# CCM_0020_receiver.net
KiCad netlist of a schematic drawn in EAGLE
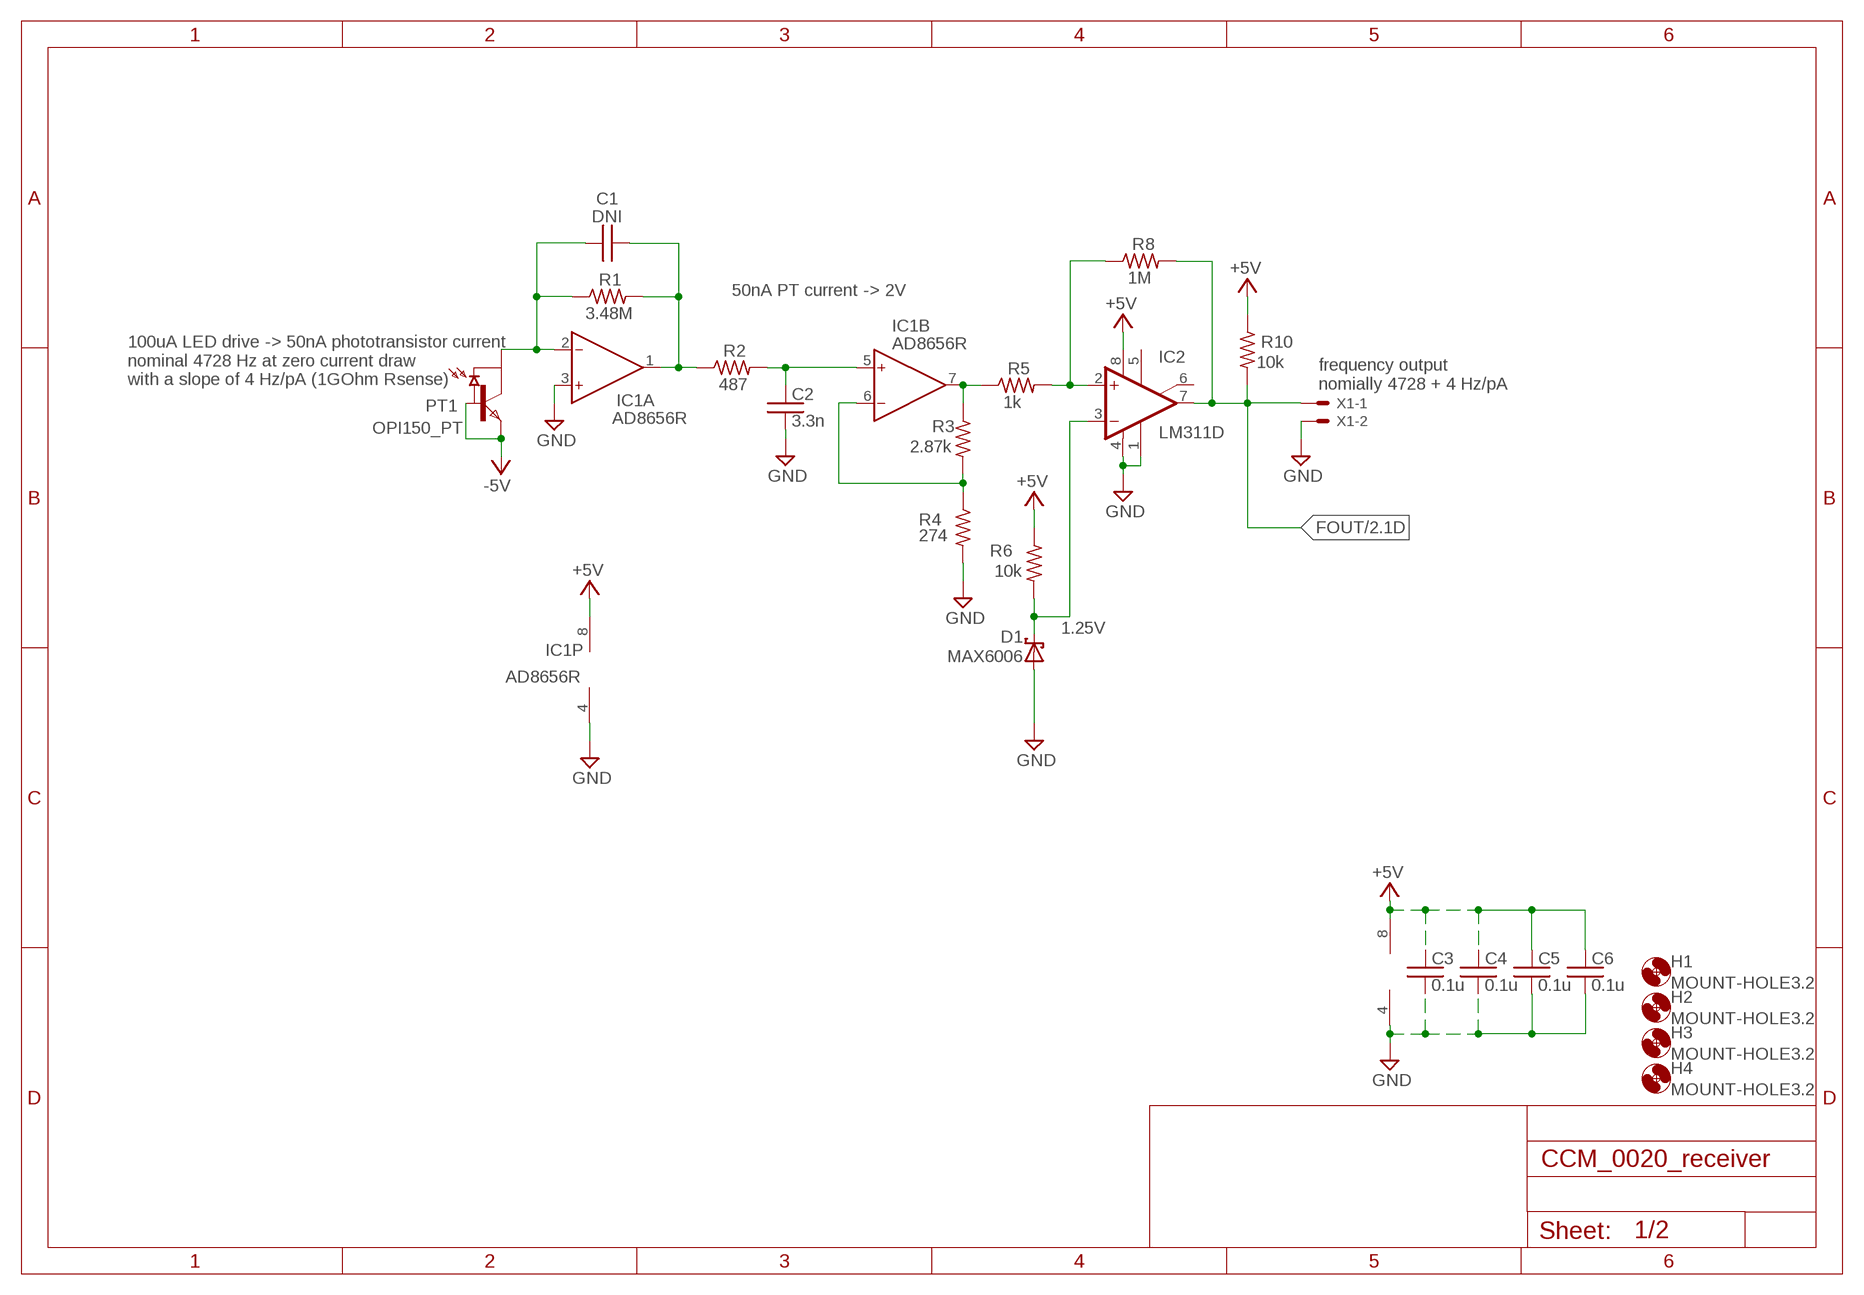
[diagram p0: schematic, sheet 1]
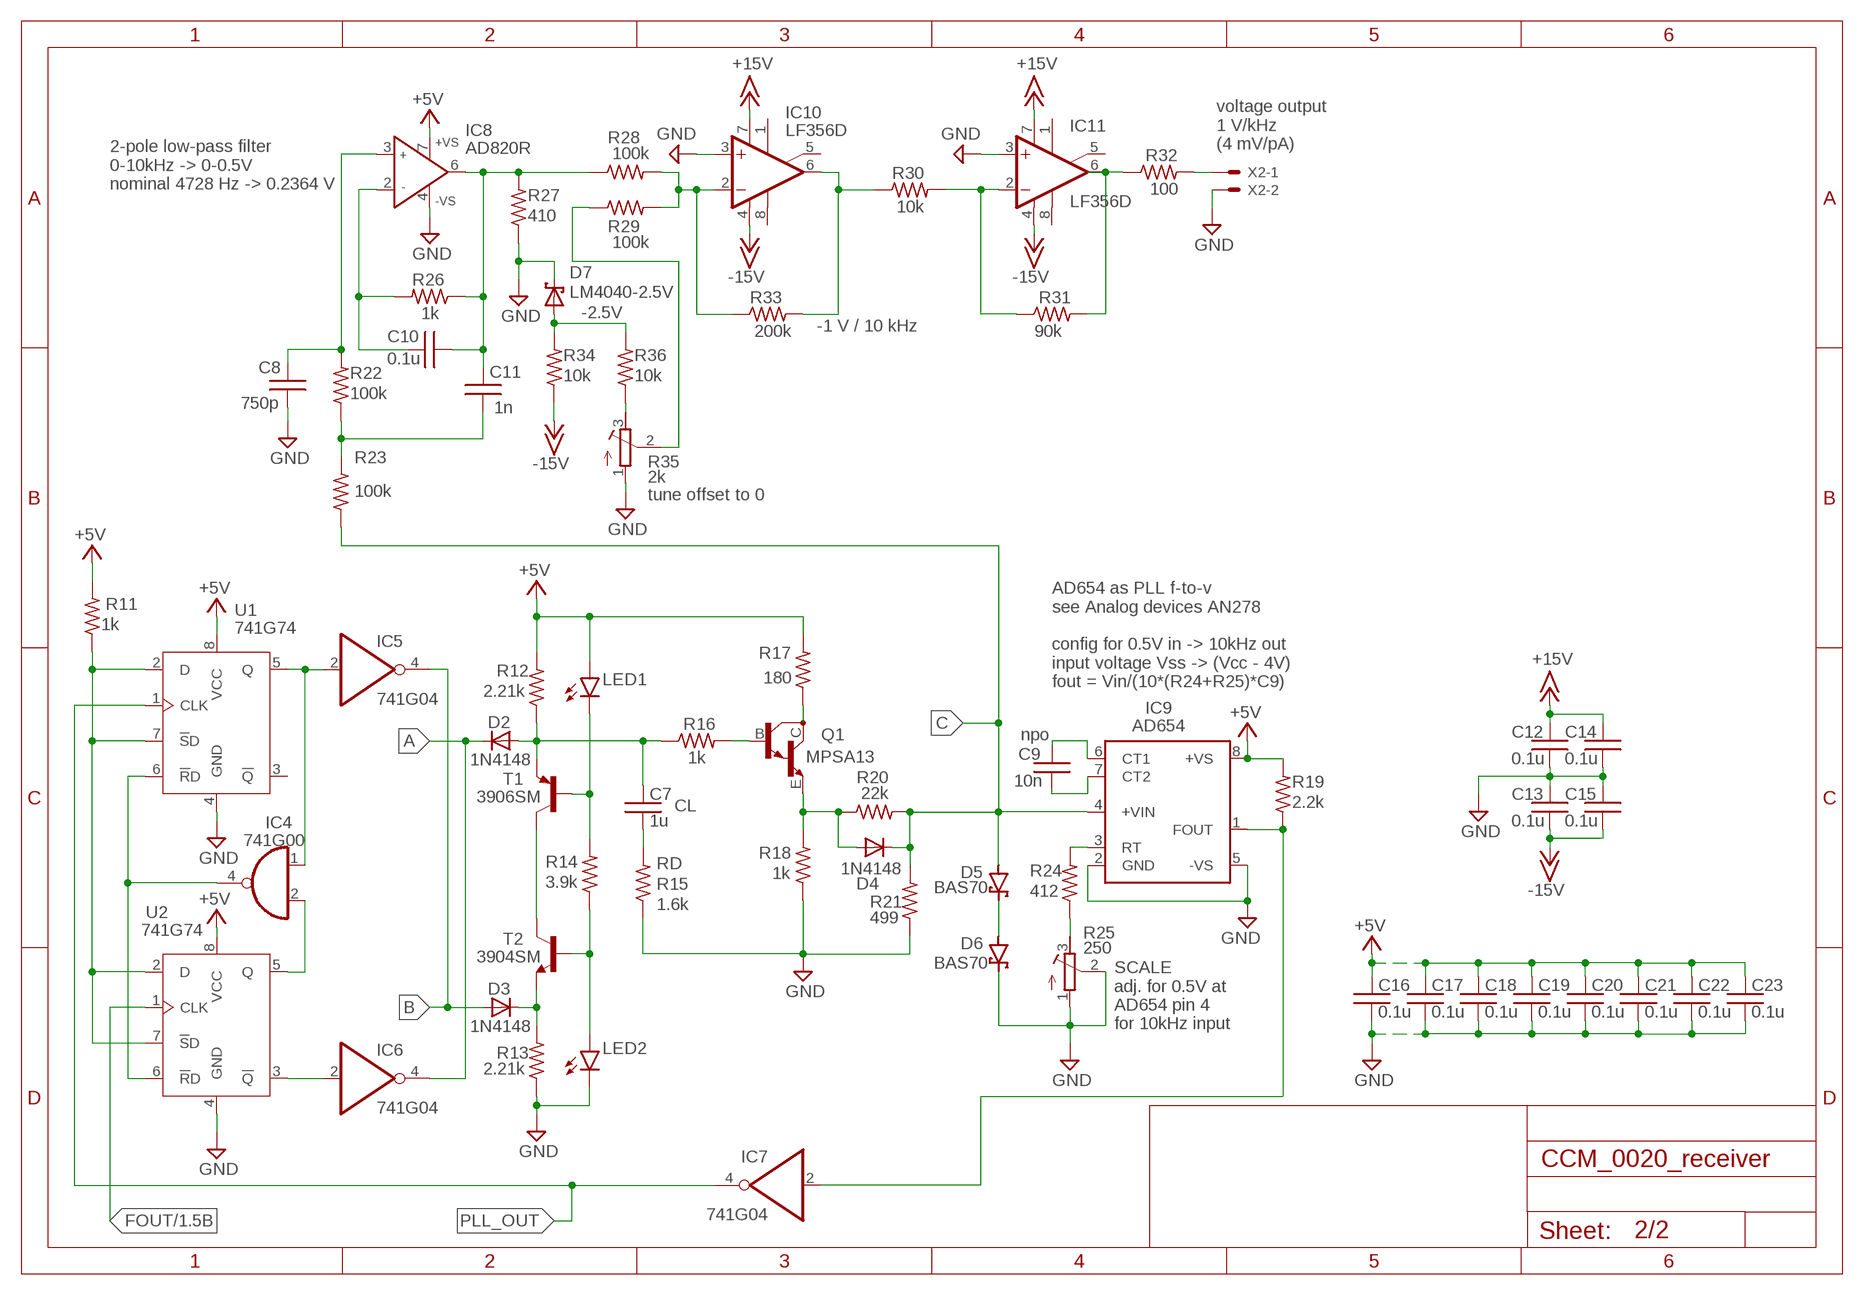
[diagram p1: schematic, sheet 2]

(export (version "E")
  (design (tool "Eeschema 10.0.6"))
  (components
    (comp (ref "C1")
      (value "DNI")
      (footprint "eagle-import:0603")
      (libsource (lib "eagle-import") (part "C0603"))
    )
    (comp (ref "C2")
      (value "3.3n")
      (footprint "eagle-import:0603")
      (libsource (lib "eagle-import") (part "C0603"))
    )
    (comp (ref "C3")
      (value "0.1u")
      (footprint "eagle-import:0603")
      (libsource (lib "eagle-import") (part "C0603"))
    )
    (comp (ref "C4")
      (value "0.1u")
      (footprint "eagle-import:0603")
      (libsource (lib "eagle-import") (part "C0603"))
    )
    (comp (ref "C5")
      (value "0.1u")
      (footprint "eagle-import:0603")
      (libsource (lib "eagle-import") (part "C0603"))
    )
    (comp (ref "C6")
      (value "0.1u")
      (footprint "eagle-import:0603")
      (libsource (lib "eagle-import") (part "C0603"))
    )
    (comp (ref "D1")
      (value "MAX6006")
      (footprint "eagle-import:SOT23")
      (libsource (lib "eagle-import") (part "LM4040"))
    )
    (comp (ref "H1")
      (value "MOUNT-HOLE3.2")
      (footprint "eagle-import:3,2")
      (libsource (lib "eagle-import") (part "MOUNT-HOLE3.2"))
    )
    (comp (ref "H2")
      (value "MOUNT-HOLE3.2")
      (footprint "eagle-import:3,2")
      (libsource (lib "eagle-import") (part "MOUNT-HOLE3.2"))
    )
    (comp (ref "H3")
      (value "MOUNT-HOLE3.2")
      (footprint "eagle-import:3,2")
      (libsource (lib "eagle-import") (part "MOUNT-HOLE3.2"))
    )
    (comp (ref "H4")
      (value "MOUNT-HOLE3.2")
      (footprint "eagle-import:3,2")
      (libsource (lib "eagle-import") (part "MOUNT-HOLE3.2"))
    )
    (comp (ref "IC1")
      (value "AD8656R")
      (footprint "eagle-import:SO8")
      (fields (field (name "MPN") "AD8656ARZ"))
      (libsource (lib "eagle-import") (part "AD8656R"))
    )
    (comp (ref "IC2")
      (value "LM311D")
      (footprint "eagle-import:SO08")
      (libsource (lib "eagle-import") (part "LM311D"))
    )
    (comp (ref "IC3")
      (value "LT1495")
      (footprint "eagle-import:SO08")
      (libsource (lib "eagle-import") (part "LM393D"))
    )
    (comp (ref "PT1")
      (value "OPI150_PT")
      (footprint "eagle-import:OPI150_PHOTOTRANSISTOR")
      (libsource (lib "eagle-import") (part "OPI150_PHOTOTRANSISTOR"))
    )
    (comp (ref "R1")
      (value "3.48M")
      (footprint "eagle-import:0603")
      (libsource (lib "eagle-import") (part "R0603"))
    )
    (comp (ref "R2")
      (value "487")
      (footprint "eagle-import:0603")
      (libsource (lib "eagle-import") (part "R0603"))
    )
    (comp (ref "R3")
      (value "2.87k")
      (footprint "eagle-import:0603")
      (libsource (lib "eagle-import") (part "R0603"))
    )
    (comp (ref "R4")
      (value "274")
      (footprint "eagle-import:0603")
      (libsource (lib "eagle-import") (part "R0603"))
    )
    (comp (ref "R5")
      (value "1k")
      (footprint "eagle-import:0603")
      (libsource (lib "eagle-import") (part "R0603"))
    )
    (comp (ref "R6")
      (value "10k")
      (footprint "eagle-import:0603")
      (libsource (lib "eagle-import") (part "R0603"))
    )
    (comp (ref "R8")
      (value "1M")
      (footprint "eagle-import:0603")
      (libsource (lib "eagle-import") (part "R0603"))
    )
    (comp (ref "R10")
      (value "10k")
      (footprint "eagle-import:0603")
      (libsource (lib "eagle-import") (part "R0603"))
    )
    (comp (ref "X1")
      (value "22-23-2021")
      (footprint "eagle-import:22-23-2021")
      (fields (field (name "MF") "MOLEX"))
      (libsource (lib "eagle-import") (part "22-23-2021"))
    )
    (comp (ref "C7")
      (value "1u")
      (footprint "eagle-import:0603")
      (libsource (lib "eagle-import") (part "C0603"))
    )
    (comp (ref "C8")
      (value "750p")
      (footprint "eagle-import:0603")
      (libsource (lib "eagle-import") (part "C0603"))
    )
    (comp (ref "C9")
      (value "10n")
      (footprint "eagle-import:0603")
      (libsource (lib "eagle-import") (part "C0603"))
    )
    (comp (ref "C10")
      (value "0.1u")
      (footprint "eagle-import:0603")
      (libsource (lib "eagle-import") (part "C0603"))
    )
    (comp (ref "C11")
      (value "1n")
      (footprint "eagle-import:0603")
      (libsource (lib "eagle-import") (part "C0603"))
    )
    (comp (ref "C12")
      (value "0.1u")
      (footprint "eagle-import:0603")
      (libsource (lib "eagle-import") (part "C0603"))
    )
    (comp (ref "C13")
      (value "0.1u")
      (footprint "eagle-import:0603")
      (libsource (lib "eagle-import") (part "C0603"))
    )
    (comp (ref "C14")
      (value "0.1u")
      (footprint "eagle-import:0603")
      (libsource (lib "eagle-import") (part "C0603"))
    )
    (comp (ref "C15")
      (value "0.1u")
      (footprint "eagle-import:0603")
      (libsource (lib "eagle-import") (part "C0603"))
    )
    (comp (ref "C16")
      (value "0.1u")
      (footprint "eagle-import:0603")
      (libsource (lib "eagle-import") (part "C0603"))
    )
    (comp (ref "C17")
      (value "0.1u")
      (footprint "eagle-import:0603")
      (libsource (lib "eagle-import") (part "C0603"))
    )
    (comp (ref "C18")
      (value "0.1u")
      (footprint "eagle-import:0603")
      (libsource (lib "eagle-import") (part "C0603"))
    )
    (comp (ref "C19")
      (value "0.1u")
      (footprint "eagle-import:0603")
      (libsource (lib "eagle-import") (part "C0603"))
    )
    (comp (ref "C20")
      (value "0.1u")
      (footprint "eagle-import:0603")
      (libsource (lib "eagle-import") (part "C0603"))
    )
    (comp (ref "C21")
      (value "0.1u")
      (footprint "eagle-import:0603")
      (libsource (lib "eagle-import") (part "C0603"))
    )
    (comp (ref "C22")
      (value "0.1u")
      (footprint "eagle-import:0603")
      (libsource (lib "eagle-import") (part "C0603"))
    )
    (comp (ref "C23")
      (value "0.1u")
      (footprint "eagle-import:0603")
      (libsource (lib "eagle-import") (part "C0603"))
    )
    (comp (ref "D2")
      (value "1N4148")
      (footprint "eagle-import:SOD323_ST")
      (libsource (lib "eagle-import") (part "1N4148"))
    )
    (comp (ref "D3")
      (value "1N4148")
      (footprint "eagle-import:SOD323_ST")
      (libsource (lib "eagle-import") (part "1N4148"))
    )
    (comp (ref "D4")
      (value "1N4148")
      (footprint "eagle-import:SOD323_ST")
      (libsource (lib "eagle-import") (part "1N4148"))
    )
    (comp (ref "D5")
      (value "BAS70")
      (footprint "eagle-import:SOT23")
      (libsource (lib "eagle-import") (part "BAS70"))
    )
    (comp (ref "D6")
      (value "BAS70")
      (footprint "eagle-import:SOT23")
      (libsource (lib "eagle-import") (part "BAS70"))
    )
    (comp (ref "D7")
      (value "LM4040-2.5V")
      (footprint "eagle-import:SOT23")
      (libsource (lib "eagle-import") (part "LM4040"))
    )
    (comp (ref "IC4")
      (value "741G00")
      (footprint "eagle-import:SOT23-5")
      (libsource (lib "eagle-import") (part "741G00DBVAHC"))
    )
    (comp (ref "IC5")
      (value "741G04")
      (footprint "eagle-import:SOT23-5")
      (libsource (lib "eagle-import") (part "741G04DBVAHC"))
    )
    (comp (ref "IC6")
      (value "741G04")
      (footprint "eagle-import:SOT23-5")
      (libsource (lib "eagle-import") (part "741G04DBVAHC"))
    )
    (comp (ref "IC7")
      (value "741G04")
      (footprint "eagle-import:SOT23-5")
      (libsource (lib "eagle-import") (part "741G04DBVAHC"))
    )
    (comp (ref "IC8")
      (value "AD820R")
      (footprint "eagle-import:SO8")
      (libsource (lib "eagle-import") (part "AD820R"))
    )
    (comp (ref "IC9")
      (value "AD654")
      (footprint "eagle-import:SO08")
      (libsource (lib "eagle-import") (part "AD654"))
    )
    (comp (ref "IC10")
      (value "LF356D")
      (footprint "eagle-import:SO08")
      (libsource (lib "eagle-import") (part "LF356D"))
    )
    (comp (ref "IC11")
      (value "LF356D")
      (footprint "eagle-import:SO08")
      (libsource (lib "eagle-import") (part "LF356D"))
    )
    (comp (ref "LED1")
      (value "LEDCHIP-LED0603")
      (footprint "eagle-import:CHIP-LED0603")
      (libsource (lib "eagle-import") (part "LEDCHIP-LED0603"))
    )
    (comp (ref "LED2")
      (value "LEDCHIP-LED0603")
      (footprint "eagle-import:CHIP-LED0603")
      (libsource (lib "eagle-import") (part "LEDCHIP-LED0603"))
    )
    (comp (ref "Q1")
      (value "MPSA13")
      (footprint "eagle-import:SOT23-BEC")
      (libsource (lib "eagle-import") (part "MMBTA13LT1"))
    )
    (comp (ref "R11")
      (value "1k")
      (footprint "eagle-import:0603")
      (libsource (lib "eagle-import") (part "R0603"))
    )
    (comp (ref "R12")
      (value "2.21k")
      (footprint "eagle-import:0603")
      (libsource (lib "eagle-import") (part "R0603"))
    )
    (comp (ref "R13")
      (value "2.21k")
      (footprint "eagle-import:0603")
      (libsource (lib "eagle-import") (part "R0603"))
    )
    (comp (ref "R14")
      (value "3.9k")
      (footprint "eagle-import:0603")
      (libsource (lib "eagle-import") (part "R0603"))
    )
    (comp (ref "R15")
      (value "1.6k")
      (footprint "eagle-import:0603")
      (libsource (lib "eagle-import") (part "R0603"))
    )
    (comp (ref "R16")
      (value "1k")
      (footprint "eagle-import:0603")
      (libsource (lib "eagle-import") (part "R0603"))
    )
    (comp (ref "R17")
      (value "180")
      (footprint "eagle-import:0603")
      (libsource (lib "eagle-import") (part "R0603"))
    )
    (comp (ref "R18")
      (value "1k")
      (footprint "eagle-import:0603")
      (libsource (lib "eagle-import") (part "R0603"))
    )
    (comp (ref "R19")
      (value "2.2k")
      (footprint "eagle-import:0603")
      (libsource (lib "eagle-import") (part "R0603"))
    )
    (comp (ref "R20")
      (value "22k")
      (footprint "eagle-import:0603")
      (libsource (lib "eagle-import") (part "R0603"))
    )
    (comp (ref "R21")
      (value "499")
      (footprint "eagle-import:0603")
      (libsource (lib "eagle-import") (part "R0603"))
    )
    (comp (ref "R22")
      (value "100k")
      (footprint "eagle-import:0603")
      (libsource (lib "eagle-import") (part "R0603"))
    )
    (comp (ref "R23")
      (value "100k")
      (footprint "eagle-import:0603")
      (libsource (lib "eagle-import") (part "R0603"))
    )
    (comp (ref "R24")
      (value "412")
      (footprint "eagle-import:0603")
      (libsource (lib "eagle-import") (part "R0603"))
    )
    (comp (ref "R25")
      (value "250")
      (footprint "eagle-import:RTRIM64Y")
      (libsource (lib "eagle-import") (part "R-TRIMM64Y"))
    )
    (comp (ref "R26")
      (value "1k")
      (footprint "eagle-import:0603")
      (libsource (lib "eagle-import") (part "R0603"))
    )
    (comp (ref "R27")
      (value "410")
      (footprint "eagle-import:0603")
      (libsource (lib "eagle-import") (part "R0603"))
    )
    (comp (ref "R28")
      (value "100k")
      (footprint "eagle-import:0603")
      (libsource (lib "eagle-import") (part "R0603"))
    )
    (comp (ref "R29")
      (value "100k")
      (footprint "eagle-import:0603")
      (libsource (lib "eagle-import") (part "R0603"))
    )
    (comp (ref "R30")
      (value "10k")
      (footprint "eagle-import:0603")
      (libsource (lib "eagle-import") (part "R0603"))
    )
    (comp (ref "R31")
      (value "90k")
      (footprint "eagle-import:0603")
      (libsource (lib "eagle-import") (part "R0603"))
    )
    (comp (ref "R32")
      (value "100")
      (footprint "eagle-import:0603")
      (libsource (lib "eagle-import") (part "R0603"))
    )
    (comp (ref "R33")
      (value "200k")
      (footprint "eagle-import:0603")
      (libsource (lib "eagle-import") (part "R0603"))
    )
    (comp (ref "R34")
      (value "10k")
      (footprint "eagle-import:0603")
      (libsource (lib "eagle-import") (part "R0603"))
    )
    (comp (ref "R35")
      (value "2k")
      (footprint "eagle-import:RTRIM64Y")
      (libsource (lib "eagle-import") (part "R-TRIMM64Y"))
    )
    (comp (ref "R36")
      (value "10k")
      (footprint "eagle-import:0603")
      (libsource (lib "eagle-import") (part "R0603"))
    )
    (comp (ref "T1")
      (value "3906SM")
      (footprint "eagle-import:SOT23-BEC")
      (libsource (lib "eagle-import") (part "-PNP-SOT23-BECMMBT3906LT1"))
    )
    (comp (ref "T2")
      (value "3904SM")
      (footprint "eagle-import:SOT23")
      (libsource (lib "eagle-import") (part "3904SM"))
    )
    (comp (ref "U1")
      (value "741G74")
      (footprint "eagle-import:TSSOP8")
      (libsource (lib "eagle-import") (part "741G74"))
    )
    (comp (ref "U2")
      (value "741G74")
      (footprint "eagle-import:TSSOP8")
      (libsource (lib "eagle-import") (part "741G74"))
    )
    (comp (ref "X2")
      (value "22-23-2021")
      (footprint "eagle-import:22-23-2021")
      (fields (field (name "MF") "MOLEX"))
      (libsource (lib "eagle-import") (part "22-23-2021"))
    )
  )
  (nets
    (net (code "1") (name "+5V") (class "Default")
      (node (ref "C16") (pin "1") (pinfunction "1_1") (pintype "passive"))
      (node (ref "C17") (pin "1") (pinfunction "1_1") (pintype "passive"))
      (node (ref "C18") (pin "1") (pinfunction "1_1") (pintype "passive"))
      (node (ref "C19") (pin "1") (pinfunction "1_1") (pintype "passive"))
      (node (ref "C20") (pin "1") (pinfunction "1_1") (pintype "passive"))
      (node (ref "C21") (pin "1") (pinfunction "1_1") (pintype "passive"))
      (node (ref "C22") (pin "1") (pinfunction "1_1") (pintype "passive"))
      (node (ref "C23") (pin "1") (pinfunction "1_1") (pintype "passive"))
      (node (ref "C3") (pin "1") (pinfunction "1_1") (pintype "passive"))
      (node (ref "C4") (pin "1") (pinfunction "1_1") (pintype "passive"))
      (node (ref "C5") (pin "1") (pinfunction "1_1") (pintype "passive"))
      (node (ref "C6") (pin "1") (pinfunction "1_1") (pintype "passive"))
      (node (ref "IC1") (pin "8") (pinfunction "V+_8") (pintype "power_in"))
      (node (ref "IC2") (pin "8") (pinfunction "V+_8") (pintype "power_in"))
      (node (ref "IC3") (pin "8") (pinfunction "V+_8") (pintype "power_in"))
      (node (ref "IC8") (pin "7") (pinfunction "+VS_7") (pintype "input"))
      (node (ref "IC9") (pin "8") (pinfunction "+VS_8") (pintype "power_in"))
      (node (ref "LED1") (pin "A") (pinfunction "A_A") (pintype "passive"))
      (node (ref "R10") (pin "1") (pinfunction "1_1") (pintype "passive"))
      (node (ref "R11") (pin "2") (pinfunction "2_2") (pintype "passive"))
      (node (ref "R12") (pin "2") (pinfunction "2_2") (pintype "passive"))
      (node (ref "R17") (pin "2") (pinfunction "2_2") (pintype "passive"))
      (node (ref "R19") (pin "2") (pinfunction "2_2") (pintype "passive"))
      (node (ref "R6") (pin "1") (pinfunction "1_1") (pintype "passive"))
      (node (ref "U1") (pin "8") (pinfunction "VCC_8") (pintype "bidirectional"))
      (node (ref "U2") (pin "8") (pinfunction "VCC_8") (pintype "bidirectional"))
    )
    (net (code "2") (name "+15V") (class "Default")
      (node (ref "C12") (pin "2") (pinfunction "2_2") (pintype "passive"))
      (node (ref "C14") (pin "2") (pinfunction "2_2") (pintype "passive"))
      (node (ref "IC10") (pin "7") (pinfunction "V+_7") (pintype "power_in"))
      (node (ref "IC11") (pin "7") (pinfunction "V+_7") (pintype "power_in"))
    )
    (net (code "3") (name "-5V") (class "Default")
      (node (ref "PT1") (pin "P4") (pinfunction "BASE_P4") (pintype "passive"))
      (node (ref "PT1") (pin "P5") (pinfunction "EMITTER_P5") (pintype "passive"))
    )
    (net (code "4") (name "-15V") (class "Default")
      (node (ref "C13") (pin "1") (pinfunction "1_1") (pintype "passive"))
      (node (ref "C15") (pin "1") (pinfunction "1_1") (pintype "passive"))
      (node (ref "IC10") (pin "4") (pinfunction "V-_4") (pintype "power_in"))
      (node (ref "IC11") (pin "4") (pinfunction "V-_4") (pintype "power_in"))
      (node (ref "R34") (pin "1") (pinfunction "1_1") (pintype "passive"))
    )
    (net (code "5") (name "A") (class "Default")
      (node (ref "D2") (pin "C") (pinfunction "C_C") (pintype "passive"))
      (node (ref "IC6") (pin "4") (pinfunction "O_4") (pintype "output"))
    )
    (net (code "6") (name "B") (class "Default")
      (node (ref "D3") (pin "A") (pinfunction "A_A") (pintype "passive"))
      (node (ref "IC5") (pin "4") (pinfunction "O_4") (pintype "output"))
    )
    (net (code "7") (name "C") (class "Default")
      (node (ref "D4") (pin "C") (pinfunction "C_C") (pintype "passive"))
      (node (ref "D5") (pin "1") (pinfunction "A_1") (pintype "passive"))
      (node (ref "IC9") (pin "4") (pinfunction "+VIN_4") (pintype "input"))
      (node (ref "R20") (pin "2") (pinfunction "2_2") (pintype "passive"))
      (node (ref "R21") (pin "2") (pinfunction "2_2") (pintype "passive"))
      (node (ref "R23") (pin "1") (pinfunction "1_1") (pintype "passive"))
    )
    (net (code "8") (name "FOUT") (class "Default")
      (node (ref "IC2") (pin "7") (pinfunction "OUT_7") (pintype "output"))
      (node (ref "R10") (pin "2") (pinfunction "2_2") (pintype "passive"))
      (node (ref "R8") (pin "2") (pinfunction "2_2") (pintype "passive"))
      (node (ref "U2") (pin "1") (pinfunction "CLK_1") (pintype "bidirectional"))
      (node (ref "X1") (pin "1") (pinfunction "S_1") (pintype "passive"))
    )
    (net (code "9") (name "GND") (class "Default")
      (node (ref "C12") (pin "1") (pinfunction "1_1") (pintype "passive"))
      (node (ref "C13") (pin "2") (pinfunction "2_2") (pintype "passive"))
      (node (ref "C14") (pin "1") (pinfunction "1_1") (pintype "passive"))
      (node (ref "C15") (pin "2") (pinfunction "2_2") (pintype "passive"))
      (node (ref "C16") (pin "2") (pinfunction "2_2") (pintype "passive"))
      (node (ref "C17") (pin "2") (pinfunction "2_2") (pintype "passive"))
      (node (ref "C18") (pin "2") (pinfunction "2_2") (pintype "passive"))
      (node (ref "C19") (pin "2") (pinfunction "2_2") (pintype "passive"))
      (node (ref "C2") (pin "2") (pinfunction "2_2") (pintype "passive"))
      (node (ref "C20") (pin "2") (pinfunction "2_2") (pintype "passive"))
      (node (ref "C21") (pin "2") (pinfunction "2_2") (pintype "passive"))
      (node (ref "C22") (pin "2") (pinfunction "2_2") (pintype "passive"))
      (node (ref "C23") (pin "2") (pinfunction "2_2") (pintype "passive"))
      (node (ref "C3") (pin "2") (pinfunction "2_2") (pintype "passive"))
      (node (ref "C4") (pin "2") (pinfunction "2_2") (pintype "passive"))
      (node (ref "C5") (pin "2") (pinfunction "2_2") (pintype "passive"))
      (node (ref "C6") (pin "2") (pinfunction "2_2") (pintype "passive"))
      (node (ref "C8") (pin "1") (pinfunction "1_1") (pintype "passive"))
      (node (ref "D1") (pin "2") (pinfunction "A_2") (pintype "passive"))
      (node (ref "D6") (pin "3") (pinfunction "C_3") (pintype "passive"))
      (node (ref "D7") (pin "1") (pinfunction "C_1") (pintype "passive"))
      (node (ref "IC1") (pin "3") (pinfunction "IN+_3") (pintype "input"))
      (node (ref "IC1") (pin "4") (pinfunction "V-_4") (pintype "power_in"))
      (node (ref "IC10") (pin "3") (pinfunction "+IN_3") (pintype "input"))
      (node (ref "IC11") (pin "3") (pinfunction "+IN_3") (pintype "input"))
      (node (ref "IC2") (pin "1") (pinfunction "GND_1") (pintype "passive"))
      (node (ref "IC2") (pin "4") (pinfunction "V-_4") (pintype "power_in"))
      (node (ref "IC3") (pin "4") (pinfunction "V-_4") (pintype "power_in"))
      (node (ref "IC8") (pin "4") (pinfunction "-VS_4") (pintype "input"))
      (node (ref "IC9") (pin "2") (pinfunction "GND_2") (pintype "power_in"))
      (node (ref "IC9") (pin "5") (pinfunction "-VS_5") (pintype "power_in"))
      (node (ref "LED2") (pin "C") (pinfunction "C_C") (pintype "passive"))
      (node (ref "R13") (pin "1") (pinfunction "1_1") (pintype "passive"))
      (node (ref "R15") (pin "1") (pinfunction "1_1") (pintype "passive"))
      (node (ref "R18") (pin "1") (pinfunction "1_1") (pintype "passive"))
      (node (ref "R21") (pin "1") (pinfunction "1_1") (pintype "passive"))
      (node (ref "R25") (pin "1") (pinfunction "A_1") (pintype "passive"))
      (node (ref "R25") (pin "2") (pinfunction "S_2") (pintype "passive"))
      (node (ref "R27") (pin "1") (pinfunction "1_1") (pintype "passive"))
      (node (ref "R35") (pin "1") (pinfunction "A_1") (pintype "passive"))
      (node (ref "R4") (pin "2") (pinfunction "2_2") (pintype "passive"))
      (node (ref "U1") (pin "4") (pinfunction "GND_4") (pintype "bidirectional"))
      (node (ref "U2") (pin "4") (pinfunction "GND_4") (pintype "bidirectional"))
      (node (ref "X1") (pin "2") (pinfunction "S_2") (pintype "passive"))
      (node (ref "X2") (pin "2") (pinfunction "S_2") (pintype "passive"))
    )
    (net (code "10") (name "Net-(C7-Pad1)") (class "Default")
      (node (ref "C7") (pin "1") (pinfunction "1_1") (pintype "passive"))
      (node (ref "D2") (pin "A") (pinfunction "A_A") (pintype "passive"))
      (node (ref "R12") (pin "1") (pinfunction "1_1") (pintype "passive"))
      (node (ref "R16") (pin "1") (pinfunction "1_1") (pintype "passive"))
      (node (ref "T1") (pin "E") (pinfunction "E_E") (pintype "passive"))
    )
    (net (code "11") (name "Net-(C7-Pad2)") (class "Default")
      (node (ref "C7") (pin "2") (pinfunction "2_2") (pintype "passive"))
      (node (ref "R15") (pin "2") (pinfunction "2_2") (pintype "passive"))
    )
    (net (code "12") (name "Net-(C11-Pad1)") (class "Default")
      (node (ref "C11") (pin "1") (pinfunction "1_1") (pintype "passive"))
      (node (ref "R22") (pin "1") (pinfunction "1_1") (pintype "passive"))
      (node (ref "R23") (pin "2") (pinfunction "2_2") (pintype "passive"))
    )
    (net (code "13") (name "Net-(D1-C)") (class "Default")
      (node (ref "D1") (pin "1") (pinfunction "C_1") (pintype "passive"))
      (node (ref "IC2") (pin "3") (pinfunction "-IN_3") (pintype "input"))
      (node (ref "R6") (pin "2") (pinfunction "2_2") (pintype "passive"))
    )
    (net (code "14") (name "Net-(D4-PadA)") (class "Default")
      (node (ref "D4") (pin "A") (pinfunction "A_A") (pintype "passive"))
      (node (ref "Q1") (pin "E") (pinfunction "E_E") (pintype "passive"))
      (node (ref "R18") (pin "2") (pinfunction "2_2") (pintype "passive"))
      (node (ref "R20") (pin "1") (pinfunction "1_1") (pintype "passive"))
    )
    (net (code "15") (name "Net-(D5-C)") (class "Default")
      (node (ref "D5") (pin "3") (pinfunction "C_3") (pintype "passive"))
      (node (ref "D6") (pin "1") (pinfunction "A_1") (pintype "passive"))
    )
    (net (code "16") (name "Net-(D7-A)") (class "Default")
      (node (ref "D7") (pin "2") (pinfunction "A_2") (pintype "passive"))
      (node (ref "R34") (pin "2") (pinfunction "2_2") (pintype "passive"))
      (node (ref "R36") (pin "2") (pinfunction "2_2") (pintype "passive"))
    )
    (net (code "17") (name "Net-(IC1A-IN-)") (class "Default")
      (node (ref "C1") (pin "1") (pinfunction "1_1") (pintype "passive"))
      (node (ref "IC1") (pin "2") (pinfunction "IN-_2") (pintype "input"))
      (node (ref "PT1") (pin "P3") (pinfunction "COLLECTOR_P3") (pintype "passive"))
      (node (ref "R1") (pin "1") (pinfunction "1_1") (pintype "passive"))
    )
    (net (code "18") (name "Net-(IC1A-OUT)") (class "Default")
      (node (ref "C1") (pin "2") (pinfunction "2_2") (pintype "passive"))
      (node (ref "IC1") (pin "1") (pinfunction "OUT_1") (pintype "output"))
      (node (ref "R1") (pin "2") (pinfunction "2_2") (pintype "passive"))
      (node (ref "R2") (pin "1") (pinfunction "1_1") (pintype "passive"))
    )
    (net (code "19") (name "Net-(IC1B-IN+)") (class "Default")
      (node (ref "C2") (pin "1") (pinfunction "1_1") (pintype "passive"))
      (node (ref "IC1") (pin "5") (pinfunction "IN+_5") (pintype "input"))
      (node (ref "R2") (pin "2") (pinfunction "2_2") (pintype "passive"))
    )
    (net (code "20") (name "Net-(IC1B-IN-)") (class "Default")
      (node (ref "IC1") (pin "6") (pinfunction "IN-_6") (pintype "input"))
      (node (ref "R3") (pin "2") (pinfunction "2_2") (pintype "passive"))
      (node (ref "R4") (pin "1") (pinfunction "1_1") (pintype "passive"))
    )
    (net (code "21") (name "Net-(IC1B-OUT)") (class "Default")
      (node (ref "IC1") (pin "7") (pinfunction "OUT_7") (pintype "output"))
      (node (ref "R3") (pin "1") (pinfunction "1_1") (pintype "passive"))
      (node (ref "R5") (pin "1") (pinfunction "1_1") (pintype "passive"))
    )
    (net (code "22") (name "Net-(IC2-+IN)") (class "Default")
      (node (ref "IC2") (pin "2") (pinfunction "+IN_2") (pintype "input"))
      (node (ref "R5") (pin "2") (pinfunction "2_2") (pintype "passive"))
      (node (ref "R8") (pin "1") (pinfunction "1_1") (pintype "passive"))
    )
    (net (code "23") (name "Net-(IC4A-I0)") (class "Default")
      (node (ref "IC4") (pin "1") (pinfunction "I0_1") (pintype "input"))
      (node (ref "IC5") (pin "2") (pinfunction "I_2") (pintype "input"))
      (node (ref "U1") (pin "5") (pinfunction "Q_5") (pintype "bidirectional"))
    )
    (net (code "24") (name "Net-(IC4A-I1)") (class "Default")
      (node (ref "IC4") (pin "2") (pinfunction "I1_2") (pintype "input"))
      (node (ref "U2") (pin "5") (pinfunction "Q_5") (pintype "bidirectional"))
    )
    (net (code "25") (name "Net-(IC4A-O)") (class "Default")
      (node (ref "IC4") (pin "4") (pinfunction "O_4") (pintype "output"))
      (node (ref "U1") (pin "6") (pinfunction "~{R}D_6") (pintype "bidirectional"))
      (node (ref "U2") (pin "6") (pinfunction "~{R}D_6") (pintype "bidirectional"))
    )
    (net (code "26") (name "Net-(IC6A-I)") (class "Default")
      (node (ref "IC6") (pin "2") (pinfunction "I_2") (pintype "input"))
      (node (ref "U2") (pin "3") (pinfunction "~{Q}_3") (pintype "bidirectional"))
    )
    (net (code "27") (name "Net-(IC7A-I)") (class "Default")
      (node (ref "IC7") (pin "2") (pinfunction "I_2") (pintype "input"))
      (node (ref "IC9") (pin "1") (pinfunction "FOUT_1") (pintype "open_collector"))
      (node (ref "R19") (pin "1") (pinfunction "1_1") (pintype "passive"))
    )
    (net (code "28") (name "Net-(IC8-IN+)") (class "Default")
      (node (ref "C8") (pin "2") (pinfunction "2_2") (pintype "passive"))
      (node (ref "IC8") (pin "3") (pinfunction "IN+_3") (pintype "input"))
      (node (ref "R22") (pin "2") (pinfunction "2_2") (pintype "passive"))
    )
    (net (code "29") (name "Net-(IC8-IN-)") (class "Default")
      (node (ref "C10") (pin "1") (pinfunction "1_1") (pintype "passive"))
      (node (ref "IC8") (pin "2") (pinfunction "IN-_2") (pintype "input"))
      (node (ref "R26") (pin "2") (pinfunction "2_2") (pintype "passive"))
    )
    (net (code "30") (name "Net-(IC8-OUT)") (class "Default")
      (node (ref "C10") (pin "2") (pinfunction "2_2") (pintype "passive"))
      (node (ref "C11") (pin "2") (pinfunction "2_2") (pintype "passive"))
      (node (ref "IC8") (pin "6") (pinfunction "OUT_6") (pintype "output"))
      (node (ref "R26") (pin "1") (pinfunction "1_1") (pintype "passive"))
      (node (ref "R27") (pin "2") (pinfunction "2_2") (pintype "passive"))
      (node (ref "R28") (pin "1") (pinfunction "1_1") (pintype "passive"))
    )
    (net (code "31") (name "Net-(IC9-CT1)") (class "Default")
      (node (ref "C9") (pin "1") (pinfunction "1_1") (pintype "passive"))
      (node (ref "IC9") (pin "6") (pinfunction "CT1_6") (pintype "passive"))
    )
    (net (code "32") (name "Net-(IC9-CT2)") (class "Default")
      (node (ref "C9") (pin "2") (pinfunction "2_2") (pintype "passive"))
      (node (ref "IC9") (pin "7") (pinfunction "CT2_7") (pintype "passive"))
    )
    (net (code "33") (name "Net-(IC9-RT)") (class "Default")
      (node (ref "IC9") (pin "3") (pinfunction "RT_3") (pintype "passive"))
      (node (ref "R24") (pin "2") (pinfunction "2_2") (pintype "passive"))
    )
    (net (code "34") (name "Net-(IC10--IN)") (class "Default")
      (node (ref "IC10") (pin "2") (pinfunction "-IN_2") (pintype "input"))
      (node (ref "R28") (pin "2") (pinfunction "2_2") (pintype "passive"))
      (node (ref "R29") (pin "2") (pinfunction "2_2") (pintype "passive"))
      (node (ref "R33") (pin "1") (pinfunction "1_1") (pintype "passive"))
    )
    (net (code "35") (name "Net-(IC10-OUT)") (class "Default")
      (node (ref "IC10") (pin "6") (pinfunction "OUT_6") (pintype "output"))
      (node (ref "R30") (pin "1") (pinfunction "1_1") (pintype "passive"))
      (node (ref "R33") (pin "2") (pinfunction "2_2") (pintype "passive"))
    )
    (net (code "36") (name "Net-(IC11--IN)") (class "Default")
      (node (ref "IC11") (pin "2") (pinfunction "-IN_2") (pintype "input"))
      (node (ref "R30") (pin "2") (pinfunction "2_2") (pintype "passive"))
      (node (ref "R31") (pin "1") (pinfunction "1_1") (pintype "passive"))
    )
    (net (code "37") (name "Net-(IC11-OUT)") (class "Default")
      (node (ref "IC11") (pin "6") (pinfunction "OUT_6") (pintype "output"))
      (node (ref "R31") (pin "2") (pinfunction "2_2") (pintype "passive"))
      (node (ref "R32") (pin "1") (pinfunction "1_1") (pintype "passive"))
    )
    (net (code "38") (name "Net-(LED1-PadC)") (class "Default")
      (node (ref "LED1") (pin "C") (pinfunction "C_C") (pintype "passive"))
      (node (ref "R14") (pin "2") (pinfunction "2_2") (pintype "passive"))
      (node (ref "T1") (pin "B") (pinfunction "B_B") (pintype "passive"))
    )
    (net (code "39") (name "Net-(Q1-PadB)") (class "Default")
      (node (ref "Q1") (pin "B") (pinfunction "B_B") (pintype "passive"))
      (node (ref "R16") (pin "2") (pinfunction "2_2") (pintype "passive"))
    )
    (net (code "40") (name "Net-(Q1-PadC)") (class "Default")
      (node (ref "Q1") (pin "C") (pinfunction "C_C") (pintype "passive"))
      (node (ref "R17") (pin "1") (pinfunction "1_1") (pintype "passive"))
    )
    (net (code "41") (name "Net-(R25-E)") (class "Default")
      (node (ref "R24") (pin "1") (pinfunction "1_1") (pintype "passive"))
      (node (ref "R25") (pin "3") (pinfunction "E_3") (pintype "passive"))
    )
    (net (code "42") (name "Net-(R35-E)") (class "Default")
      (node (ref "R35") (pin "3") (pinfunction "E_3") (pintype "passive"))
      (node (ref "R36") (pin "1") (pinfunction "1_1") (pintype "passive"))
    )
    (net (code "43") (name "Net-(R35-S)") (class "Default")
      (node (ref "R29") (pin "1") (pinfunction "1_1") (pintype "passive"))
      (node (ref "R35") (pin "2") (pinfunction "S_2") (pintype "passive"))
    )
    (net (code "44") (name "Net-(T2-B)") (class "Default")
      (node (ref "LED2") (pin "A") (pinfunction "A_A") (pintype "passive"))
      (node (ref "R14") (pin "1") (pinfunction "1_1") (pintype "passive"))
      (node (ref "T2") (pin "1") (pinfunction "B_1") (pintype "passive"))
    )
    (net (code "45") (name "Net-(T2-C)") (class "Default")
      (node (ref "T1") (pin "C") (pinfunction "C_C") (pintype "passive"))
      (node (ref "T2") (pin "3") (pinfunction "C_3") (pintype "passive"))
    )
    (net (code "46") (name "Net-(T2-E)") (class "Default")
      (node (ref "D3") (pin "C") (pinfunction "C_C") (pintype "passive"))
      (node (ref "R13") (pin "2") (pinfunction "2_2") (pintype "passive"))
      (node (ref "T2") (pin "2") (pinfunction "E_2") (pintype "passive"))
    )
    (net (code "47") (name "Net-(U1-D)") (class "Default")
      (node (ref "R11") (pin "1") (pinfunction "1_1") (pintype "passive"))
      (node (ref "U1") (pin "2") (pinfunction "D_2") (pintype "bidirectional"))
      (node (ref "U1") (pin "7") (pinfunction "~{S}D_7") (pintype "bidirectional"))
      (node (ref "U2") (pin "2") (pinfunction "D_2") (pintype "bidirectional"))
      (node (ref "U2") (pin "7") (pinfunction "~{S}D_7") (pintype "bidirectional"))
    )
    (net (code "48") (name "Net-(X2A-S)") (class "Default")
      (node (ref "R32") (pin "2") (pinfunction "2_2") (pintype "passive"))
      (node (ref "X2") (pin "1") (pinfunction "S_1") (pintype "passive"))
    )
    (net (code "49") (name "PLL_OUT") (class "Default")
      (node (ref "IC7") (pin "4") (pinfunction "O_4") (pintype "output"))
      (node (ref "U1") (pin "1") (pinfunction "CLK_1") (pintype "bidirectional"))
    )
    (net (code "50") (name "unconnected-(IC2-ON-Pad5)") (class "Default")
      (node (ref "IC2") (pin "5") (pinfunction "ON_5") (pintype "passive"))
    )
    (net (code "51") (name "unconnected-(IC2-ON{slash}STR-Pad6)") (class "Default")
      (node (ref "IC2") (pin "6") (pinfunction "ON/STR_6") (pintype "passive"))
    )
    (net (code "52") (name "unconnected-(IC10-ON1-Pad1)") (class "Default")
      (node (ref "IC10") (pin "1") (pinfunction "ON1_1") (pintype "passive"))
    )
    (net (code "53") (name "unconnected-(IC10-ON2-Pad5)") (class "Default")
      (node (ref "IC10") (pin "5") (pinfunction "ON2_5") (pintype "passive"))
    )
    (net (code "54") (name "unconnected-(IC10-OPT-Pad8)") (class "Default")
      (node (ref "IC10") (pin "8") (pinfunction "OPT_8") (pintype "passive"))
    )
    (net (code "55") (name "unconnected-(IC11-ON1-Pad1)") (class "Default")
      (node (ref "IC11") (pin "1") (pinfunction "ON1_1") (pintype "passive"))
    )
    (net (code "56") (name "unconnected-(IC11-ON2-Pad5)") (class "Default")
      (node (ref "IC11") (pin "5") (pinfunction "ON2_5") (pintype "passive"))
    )
    (net (code "57") (name "unconnected-(IC11-OPT-Pad8)") (class "Default")
      (node (ref "IC11") (pin "8") (pinfunction "OPT_8") (pintype "passive"))
    )
    (net (code "58") (name "unconnected-(U1-~{Q}-Pad3)") (class "Default")
      (node (ref "U1") (pin "3") (pinfunction "~{Q}_3") (pintype "bidirectional"))
    )
  )
)
